# atmega328.net
KiCad netlist of a schematic drawn in EAGLE
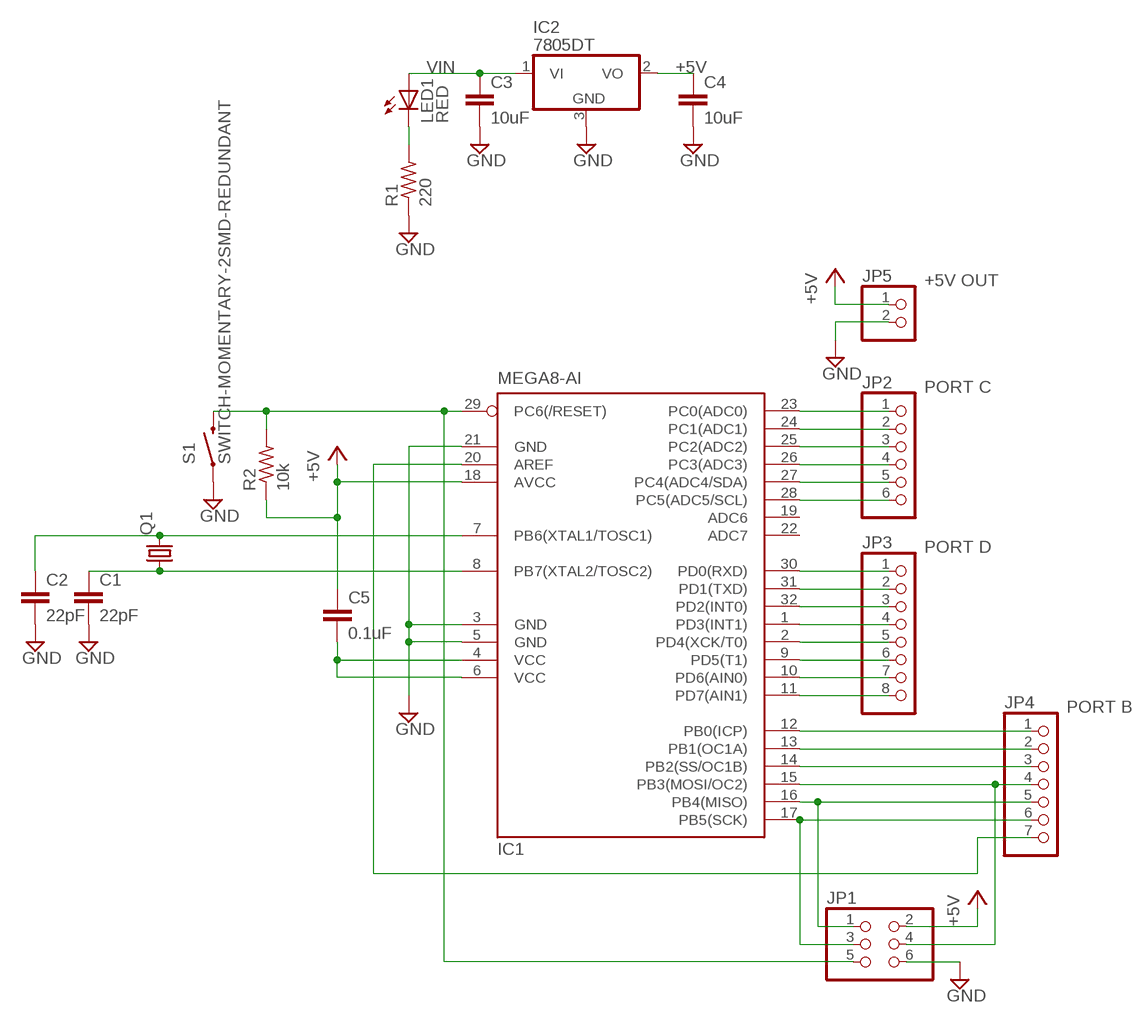
[diagram p0: schematic, sheet 1]

(export (version "E")
  (design (tool "Eeschema 10.0.6"))
  (components
    (comp (ref "C1")
      (value "22pF")
      (footprint "eagle-import:C0805")
      (libsource (lib "eagle-import") (part "C-EUC0805"))
    )
    (comp (ref "C2")
      (value "22pF")
      (footprint "eagle-import:C0805")
      (libsource (lib "eagle-import") (part "C-EUC0805"))
    )
    (comp (ref "C3")
      (value "10uF")
      (footprint "eagle-import:C0805")
      (libsource (lib "eagle-import") (part "C-EUC0805"))
    )
    (comp (ref "C4")
      (value "10uF")
      (footprint "eagle-import:C0805")
      (libsource (lib "eagle-import") (part "C-EUC0805"))
    )
    (comp (ref "C5")
      (value "0.1uF")
      (footprint "eagle-import:C0805")
      (libsource (lib "eagle-import") (part "C-EUC0805"))
    )
    (comp (ref "IC1")
      (value "MEGA8-AI")
      (footprint "eagle-import:TQFP32-08")
      (fields (field (name "MPN") "ATMEGA8-16AU"))
      (libsource (lib "eagle-import") (part "MEGA8-AI"))
    )
    (comp (ref "IC2")
      (value "7805DT")
      (footprint "eagle-import:TO252")
      (libsource (lib "eagle-import") (part "78DT05"))
    )
    (comp (ref "JP1")
      (value "PINHD-2X3")
      (footprint "eagle-import:2X03")
      (libsource (lib "eagle-import") (part "PINHD-2X3"))
    )
    (comp (ref "JP2")
      (value "PINHD-1X6")
      (footprint "eagle-import:1X06")
      (libsource (lib "eagle-import") (part "PINHD-1X6"))
    )
    (comp (ref "JP3")
      (value "PINHD-1X8")
      (footprint "eagle-import:1X08")
      (libsource (lib "eagle-import") (part "PINHD-1X8"))
    )
    (comp (ref "JP4")
      (value "PINHD-1X7")
      (footprint "eagle-import:1X07")
      (libsource (lib "eagle-import") (part "PINHD-1X7"))
    )
    (comp (ref "JP5")
      (value "PINHD-1X2")
      (footprint "eagle-import:1X02")
      (libsource (lib "eagle-import") (part "PINHD-1X2"))
    )
    (comp (ref "LED1")
      (value "RED")
      (footprint "eagle-import:CHIPLED_0805")
      (libsource (lib "eagle-import") (part "LEDCHIPLED_0805"))
    )
    (comp (ref "Q1")
      (value "CRYSTALHC49UP")
      (footprint "eagle-import:HC49UP")
      (libsource (lib "eagle-import") (part "CRYSTALHC49UP"))
    )
    (comp (ref "R1")
      (value "220")
      (footprint "eagle-import:R0805")
      (libsource (lib "eagle-import") (part "R-US_R0805"))
    )
    (comp (ref "R2")
      (value "10k")
      (footprint "eagle-import:R0805")
      (libsource (lib "eagle-import") (part "R-US_R0805"))
    )
    (comp (ref "S1")
      (value "SWITCH-MOMENTARY-2SMD-REDUNDANT")
      (footprint "eagle-import:TACTILE-SWITCH-SMD")
      (libsource (lib "eagle-import") (part "SWITCH-MOMENTARY-2SMD-REDUNDANT"))
    )
  )
  (nets
    (net (code "1") (name "+5V") (class "Default")
      (node (ref "C4") (pin "1") (pinfunction "1_1") (pintype "passive"))
      (node (ref "C5") (pin "1") (pinfunction "1_1") (pintype "passive"))
      (node (ref "IC1") (pin "18") (pinfunction "AVCC_18") (pintype "power_in"))
      (node (ref "IC2") (pin "2") (pinfunction "VO_2") (pintype "passive"))
      (node (ref "JP1") (pin "2") (pinfunction "2_2") (pintype "passive"))
      (node (ref "JP5") (pin "1") (pinfunction "1_1") (pintype "passive"))
      (node (ref "R2") (pin "1") (pinfunction "1_1") (pintype "passive"))
    )
    (net (code "2") (name "/VIN") (class "Default")
      (node (ref "C3") (pin "1") (pinfunction "1_1") (pintype "passive"))
      (node (ref "IC2") (pin "1") (pinfunction "VI_1") (pintype "input"))
      (node (ref "LED1") (pin "A") (pinfunction "A_A") (pintype "passive"))
    )
    (net (code "3") (name "GND") (class "Default")
      (node (ref "C1") (pin "2") (pinfunction "2_2") (pintype "passive"))
      (node (ref "C2") (pin "2") (pinfunction "2_2") (pintype "passive"))
      (node (ref "C3") (pin "2") (pinfunction "2_2") (pintype "passive"))
      (node (ref "C4") (pin "2") (pinfunction "2_2") (pintype "passive"))
      (node (ref "IC1") (pin "21") (pinfunction "GND_21") (pintype "power_in"))
      (node (ref "IC1") (pin "3") (pinfunction "GND_3") (pintype "power_in"))
      (node (ref "IC1") (pin "5") (pinfunction "GND_5") (pintype "power_in"))
      (node (ref "IC2") (pin "3") (pinfunction "GND_3") (pintype "passive"))
      (node (ref "JP1") (pin "6") (pinfunction "6_6") (pintype "passive"))
      (node (ref "JP5") (pin "2") (pinfunction "2_2") (pintype "passive"))
      (node (ref "R1") (pin "1") (pinfunction "1_1") (pintype "passive"))
      (node (ref "S1") (pin "1") (pinfunction "1_1") (pintype "passive"))
      (node (ref "S1") (pin "2") (pinfunction "1_2") (pintype "passive"))
    )
    (net (code "4") (name "Net-(C5-Pad2)") (class "Default")
      (node (ref "C5") (pin "2") (pinfunction "2_2") (pintype "passive"))
      (node (ref "IC1") (pin "4") (pinfunction "VCC_4") (pintype "power_in"))
      (node (ref "IC1") (pin "6") (pinfunction "VCC_6") (pintype "power_in"))
    )
    (net (code "5") (name "Net-(IC1-AREF)") (class "Default")
      (node (ref "IC1") (pin "20") (pinfunction "AREF_20") (pintype "passive"))
      (node (ref "JP4") (pin "7") (pinfunction "7_7") (pintype "passive"))
    )
    (net (code "6") (name "Net-(IC1-PB0(ICP))") (class "Default")
      (node (ref "IC1") (pin "12") (pinfunction "PB0(ICP)_12") (pintype "bidirectional"))
      (node (ref "JP4") (pin "1") (pinfunction "1_1") (pintype "passive"))
    )
    (net (code "7") (name "Net-(IC1-PB1(OC1A))") (class "Default")
      (node (ref "IC1") (pin "13") (pinfunction "PB1(OC1A)_13") (pintype "bidirectional"))
      (node (ref "JP4") (pin "2") (pinfunction "2_2") (pintype "passive"))
    )
    (net (code "8") (name "Net-(IC1-PB2(SS{slash}OC1B))") (class "Default")
      (node (ref "IC1") (pin "14") (pinfunction "PB2(SS/OC1B)_14") (pintype "bidirectional"))
      (node (ref "JP4") (pin "3") (pinfunction "3_3") (pintype "passive"))
    )
    (net (code "9") (name "Net-(IC1-PB3(MOSI{slash}OC2))") (class "Default")
      (node (ref "IC1") (pin "15") (pinfunction "PB3(MOSI/OC2)_15") (pintype "bidirectional"))
      (node (ref "JP1") (pin "4") (pinfunction "4_4") (pintype "passive"))
      (node (ref "JP4") (pin "4") (pinfunction "4_4") (pintype "passive"))
    )
    (net (code "10") (name "Net-(IC1-PB4(MISO))") (class "Default")
      (node (ref "IC1") (pin "16") (pinfunction "PB4(MISO)_16") (pintype "bidirectional"))
      (node (ref "JP1") (pin "1") (pinfunction "1_1") (pintype "passive"))
      (node (ref "JP4") (pin "5") (pinfunction "5_5") (pintype "passive"))
    )
    (net (code "11") (name "Net-(IC1-PB5(SCK))") (class "Default")
      (node (ref "IC1") (pin "17") (pinfunction "PB5(SCK)_17") (pintype "bidirectional"))
      (node (ref "JP1") (pin "3") (pinfunction "3_3") (pintype "passive"))
      (node (ref "JP4") (pin "6") (pinfunction "6_6") (pintype "passive"))
    )
    (net (code "12") (name "Net-(IC1-PB6(XTAL1{slash}TOSC1))") (class "Default")
      (node (ref "C2") (pin "1") (pinfunction "1_1") (pintype "passive"))
      (node (ref "IC1") (pin "7") (pinfunction "PB6(XTAL1/TOSC1)_7") (pintype "bidirectional"))
      (node (ref "Q1") (pin "2") (pinfunction "2_2") (pintype "passive"))
    )
    (net (code "13") (name "Net-(IC1-PB7(XTAL2{slash}TOSC2))") (class "Default")
      (node (ref "C1") (pin "1") (pinfunction "1_1") (pintype "passive"))
      (node (ref "IC1") (pin "8") (pinfunction "PB7(XTAL2/TOSC2)_8") (pintype "bidirectional"))
      (node (ref "Q1") (pin "1") (pinfunction "1_1") (pintype "passive"))
    )
    (net (code "14") (name "Net-(IC1-PC0(ADC0))") (class "Default")
      (node (ref "IC1") (pin "23") (pinfunction "PC0(ADC0)_23") (pintype "bidirectional"))
      (node (ref "JP2") (pin "1") (pinfunction "1_1") (pintype "passive"))
    )
    (net (code "15") (name "Net-(IC1-PC1(ADC1))") (class "Default")
      (node (ref "IC1") (pin "24") (pinfunction "PC1(ADC1)_24") (pintype "bidirectional"))
      (node (ref "JP2") (pin "2") (pinfunction "2_2") (pintype "passive"))
    )
    (net (code "16") (name "Net-(IC1-PC2(ADC2))") (class "Default")
      (node (ref "IC1") (pin "25") (pinfunction "PC2(ADC2)_25") (pintype "bidirectional"))
      (node (ref "JP2") (pin "3") (pinfunction "3_3") (pintype "passive"))
    )
    (net (code "17") (name "Net-(IC1-PC3(ADC3))") (class "Default")
      (node (ref "IC1") (pin "26") (pinfunction "PC3(ADC3)_26") (pintype "bidirectional"))
      (node (ref "JP2") (pin "4") (pinfunction "4_4") (pintype "passive"))
    )
    (net (code "18") (name "Net-(IC1-PC4(ADC4{slash}SDA))") (class "Default")
      (node (ref "IC1") (pin "27") (pinfunction "PC4(ADC4/SDA)_27") (pintype "bidirectional"))
      (node (ref "JP2") (pin "5") (pinfunction "5_5") (pintype "passive"))
    )
    (net (code "19") (name "Net-(IC1-PC5(ADC5{slash}SCL))") (class "Default")
      (node (ref "IC1") (pin "28") (pinfunction "PC5(ADC5/SCL)_28") (pintype "bidirectional"))
      (node (ref "JP2") (pin "6") (pinfunction "6_6") (pintype "passive"))
    )
    (net (code "20") (name "Net-(IC1-PC6({slash}RESET))") (class "Default")
      (node (ref "IC1") (pin "29") (pinfunction "PC6(/RESET)_29") (pintype "bidirectional"))
      (node (ref "JP1") (pin "5") (pinfunction "5_5") (pintype "passive"))
      (node (ref "R2") (pin "2") (pinfunction "2_2") (pintype "passive"))
      (node (ref "S1") (pin "3") (pinfunction "2_3") (pintype "passive"))
      (node (ref "S1") (pin "4") (pinfunction "2_4") (pintype "passive"))
    )
    (net (code "21") (name "Net-(IC1-PD0(RXD))") (class "Default")
      (node (ref "IC1") (pin "30") (pinfunction "PD0(RXD)_30") (pintype "bidirectional"))
      (node (ref "JP3") (pin "1") (pinfunction "1_1") (pintype "passive"))
    )
    (net (code "22") (name "Net-(IC1-PD1(TXD))") (class "Default")
      (node (ref "IC1") (pin "31") (pinfunction "PD1(TXD)_31") (pintype "bidirectional"))
      (node (ref "JP3") (pin "2") (pinfunction "2_2") (pintype "passive"))
    )
    (net (code "23") (name "Net-(IC1-PD2(INT0))") (class "Default")
      (node (ref "IC1") (pin "32") (pinfunction "PD2(INT0)_32") (pintype "bidirectional"))
      (node (ref "JP3") (pin "3") (pinfunction "3_3") (pintype "passive"))
    )
    (net (code "24") (name "Net-(IC1-PD3(INT1))") (class "Default")
      (node (ref "IC1") (pin "1") (pinfunction "PD3(INT1)_1") (pintype "bidirectional"))
      (node (ref "JP3") (pin "4") (pinfunction "4_4") (pintype "passive"))
    )
    (net (code "25") (name "Net-(IC1-PD4(XCK{slash}T0))") (class "Default")
      (node (ref "IC1") (pin "2") (pinfunction "PD4(XCK/T0)_2") (pintype "bidirectional"))
      (node (ref "JP3") (pin "5") (pinfunction "5_5") (pintype "passive"))
    )
    (net (code "26") (name "Net-(IC1-PD5(T1))") (class "Default")
      (node (ref "IC1") (pin "9") (pinfunction "PD5(T1)_9") (pintype "bidirectional"))
      (node (ref "JP3") (pin "6") (pinfunction "6_6") (pintype "passive"))
    )
    (net (code "27") (name "Net-(IC1-PD6(AIN0))") (class "Default")
      (node (ref "IC1") (pin "10") (pinfunction "PD6(AIN0)_10") (pintype "bidirectional"))
      (node (ref "JP3") (pin "7") (pinfunction "7_7") (pintype "passive"))
    )
    (net (code "28") (name "Net-(IC1-PD7(AIN1))") (class "Default")
      (node (ref "IC1") (pin "11") (pinfunction "PD7(AIN1)_11") (pintype "bidirectional"))
      (node (ref "JP3") (pin "8") (pinfunction "8_8") (pintype "passive"))
    )
    (net (code "29") (name "Net-(LED1-PadC)") (class "Default")
      (node (ref "LED1") (pin "C") (pinfunction "C_C") (pintype "passive"))
      (node (ref "R1") (pin "2") (pinfunction "2_2") (pintype "passive"))
    )
    (net (code "30") (name "unconnected-(IC1-ADC6-Pad19)") (class "Default")
      (node (ref "IC1") (pin "19") (pinfunction "ADC6_19") (pintype "bidirectional"))
    )
    (net (code "31") (name "unconnected-(IC1-ADC7-Pad22)") (class "Default")
      (node (ref "IC1") (pin "22") (pinfunction "ADC7_22") (pintype "bidirectional"))
    )
  )
)
